# BufferOpAmp.net
KiCad netlist of a schematic drawn in Altium Designer
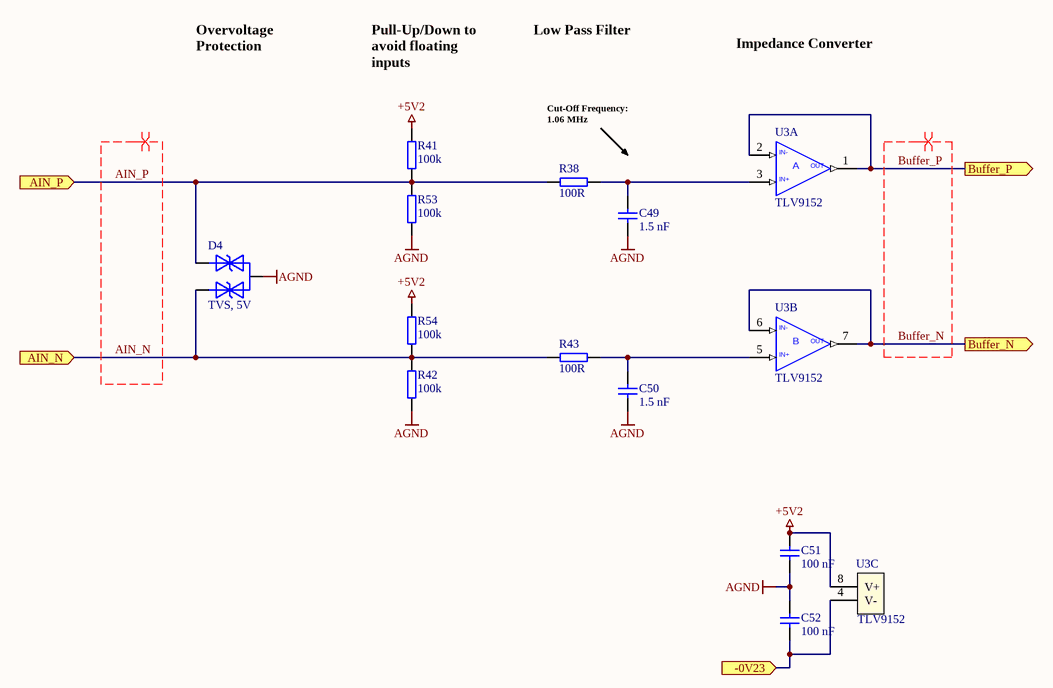
[diagram p0: BufferOpAmp.SchDoc]

(export (version "E")
  (design (tool "Eeschema 10.0.6"))
  (components
    (comp (ref "C49")
      (value "1.5 nF")
      (footprint "C_0402_TE")
      (description "Generic capacitor")
      (fields
        (field (name "MANUFACTURER PART NUMBER") "UZgen_C_0402_1.5nF_50V_NP0")
        (field (name "MANUFACTURER") "UZgen")
        (field (name "CREATED FROM") "UZgenTool")
      )
      (libsource (lib "user") (part "CAP-NP"))
    )
    (comp (ref "C50")
      (value "1.5 nF")
      (footprint "C_0402_TE")
      (description "Generic capacitor")
      (fields
        (field (name "MANUFACTURER PART NUMBER") "UZgen_C_0402_1.5nF_50V_NP0")
        (field (name "MANUFACTURER") "UZgen")
        (field (name "CREATED FROM") "UZgenTool")
      )
      (libsource (lib "user") (part "CAP-NP"))
    )
    (comp (ref "C51")
      (value "100 nF")
      (footprint "C_0402_TE")
      (description "Generic capacitor")
      (fields
        (field (name "MANUFACTURER PART NUMBER") "UZgen_C_0402_100nF_50V_X7R")
        (field (name "MANUFACTURER") "UZgen")
        (field (name "CREATED FROM") "UZgenTool")
      )
      (libsource (lib "user") (part "CAP-NP"))
    )
    (comp (ref "C52")
      (value "100 nF")
      (footprint "C_0402_TE")
      (description "Generic capacitor")
      (fields
        (field (name "MANUFACTURER PART NUMBER") "UZgen_C_0402_100nF_50V_X7R")
        (field (name "MANUFACTURER") "UZgen")
        (field (name "CREATED FROM") "UZgenTool")
      )
      (libsource (lib "user") (part "CAP-NP"))
    )
    (comp (ref "D4")
      (value "TVS, 5V")
      (footprint "SOT-23-3")
      (description "2-Line Bi-directional TVS Diode Array")
      (fields
        (field (name "MANUFACTURER PART NUMBER") "SMC05")
        (field (name "MANUFACTURER") "Leditech")
        (field (name "CREATED FROM") "AGeiger")
      )
      (libsource (lib "user") (part "TVS_BI_2_CH"))
    )
    (comp (ref "R38")
      (value "100R")
      (footprint "R_0402_TE")
      (description "Generic resistor")
      (fields
        (field (name "MANUFACTURER PART NUMBER") "UZgen_R_0402_100R")
        (field (name "MANUFACTURER") "UZgen")
        (field (name "CREATED FROM") "UZgenTool")
      )
      (libsource (lib "user") (part "RES"))
    )
    (comp (ref "R41")
      (value "100k")
      (footprint "R_0402_TE")
      (description "Generic resistor")
      (fields
        (field (name "MANUFACTURER PART NUMBER") "UZgen_R_0402_100k")
        (field (name "MANUFACTURER") "UZgen")
        (field (name "CREATED FROM") "UZgenTool")
      )
      (libsource (lib "user") (part "RES"))
    )
    (comp (ref "R42")
      (value "100k")
      (footprint "R_0402_TE")
      (description "Generic resistor")
      (fields
        (field (name "MANUFACTURER PART NUMBER") "UZgen_R_0402_100k")
        (field (name "MANUFACTURER") "UZgen")
        (field (name "CREATED FROM") "UZgenTool")
      )
      (libsource (lib "user") (part "RES"))
    )
    (comp (ref "R43")
      (value "100R")
      (footprint "R_0402_TE")
      (description "Generic resistor")
      (fields
        (field (name "MANUFACTURER PART NUMBER") "UZgen_R_0402_100R")
        (field (name "MANUFACTURER") "UZgen")
        (field (name "CREATED FROM") "UZgenTool")
      )
      (libsource (lib "user") (part "RES"))
    )
    (comp (ref "R53")
      (value "100k")
      (footprint "R_0402_TE")
      (description "Generic resistor")
      (fields
        (field (name "MANUFACTURER PART NUMBER") "UZgen_R_0402_100k")
        (field (name "MANUFACTURER") "UZgen")
        (field (name "CREATED FROM") "UZgenTool")
      )
      (libsource (lib "user") (part "RES"))
    )
    (comp (ref "R54")
      (value "100k")
      (footprint "R_0402_TE")
      (description "Generic resistor")
      (fields
        (field (name "MANUFACTURER PART NUMBER") "UZgen_R_0402_100k")
        (field (name "MANUFACTURER") "UZgen")
        (field (name "CREATED FROM") "UZgenTool")
      )
      (libsource (lib "user") (part "RES"))
    )
    (comp (ref "U3")
      (value "TLV9152")
      (footprint "MSOP-8_IPC_B")
      (description "Operationsverstärker Dual, 16-V, 4.5-MHz, low-power operational amplifier 8-VSSOP -40 to 125")
      (fields
        (field (name "MANUFACTURER PART NUMBER") "TLV9152IDGKR")
        (field (name "MANUFACTURER") "Texas Instruments")
        (field (name "CREATED FROM") "AGeiger")
      )
      (libsource (lib "user") (part "AD8629ARZ"))
    )
  )
  (nets
    (net (code "1") (name "+5V2") (class "Default")
      (node (ref "C51") (pin "1") (pinfunction "1_1") (pintype "passive"))
      (node (ref "R41") (pin "2") (pinfunction "2_2") (pintype "passive"))
      (node (ref "R54") (pin "2") (pinfunction "2_2") (pintype "passive"))
      (node (ref "U3") (pin "8") (pinfunction "V+_8") (pintype "power_in"))
    )
    (net (code "2") (name "/-0V23") (class "Default")
      (node (ref "C52") (pin "2") (pinfunction "2_2") (pintype "passive"))
      (node (ref "U3") (pin "4") (pinfunction "V-_4") (pintype "power_in"))
    )
    (net (code "3") (name "/AIN_N") (class "Default")
      (node (ref "D4") (pin "2") (pinfunction "K2_2") (pintype "passive"))
      (node (ref "R42") (pin "2") (pinfunction "2_2") (pintype "passive"))
      (node (ref "R43") (pin "1") (pinfunction "1_1") (pintype "passive"))
      (node (ref "R54") (pin "1") (pinfunction "1_1") (pintype "passive"))
    )
    (net (code "4") (name "/AIN_P") (class "Default")
      (node (ref "D4") (pin "1") (pinfunction "K1_1") (pintype "passive"))
      (node (ref "R38") (pin "1") (pinfunction "1_1") (pintype "passive"))
      (node (ref "R41") (pin "1") (pinfunction "1_1") (pintype "passive"))
      (node (ref "R53") (pin "2") (pinfunction "2_2") (pintype "passive"))
    )
    (net (code "5") (name "/Buffer_N") (class "Default")
      (node (ref "U3") (pin "6") (pinfunction "-IN_B_6") (pintype "input"))
      (node (ref "U3") (pin "7") (pinfunction "OUT_B_7") (pintype "output"))
    )
    (net (code "6") (name "/Buffer_P") (class "Default")
      (node (ref "U3") (pin "1") (pinfunction "OUT_A_1") (pintype "output"))
      (node (ref "U3") (pin "2") (pinfunction "-IN_A_2") (pintype "input"))
    )
    (net (code "7") (name "AGND") (class "Default")
      (node (ref "C49") (pin "1") (pinfunction "1_1") (pintype "passive"))
      (node (ref "C50") (pin "1") (pinfunction "1_1") (pintype "passive"))
      (node (ref "C51") (pin "2") (pinfunction "2_2") (pintype "passive"))
      (node (ref "C52") (pin "1") (pinfunction "1_1") (pintype "passive"))
      (node (ref "D4") (pin "3") (pinfunction "A_3") (pintype "passive"))
      (node (ref "R42") (pin "1") (pinfunction "1_1") (pintype "passive"))
      (node (ref "R53") (pin "1") (pinfunction "1_1") (pintype "passive"))
    )
    (net (code "8") (name "Net-(U3A-+IN_A)") (class "Default")
      (node (ref "C49") (pin "2") (pinfunction "2_2") (pintype "passive"))
      (node (ref "R38") (pin "2") (pinfunction "2_2") (pintype "passive"))
      (node (ref "U3") (pin "3") (pinfunction "+IN_A_3") (pintype "input"))
    )
    (net (code "9") (name "Net-(U3B-+IN_B)") (class "Default")
      (node (ref "C50") (pin "2") (pinfunction "2_2") (pintype "passive"))
      (node (ref "R43") (pin "2") (pinfunction "2_2") (pintype "passive"))
      (node (ref "U3") (pin "5") (pinfunction "+IN_B_5") (pintype "input"))
    )
  )
)
